# 27.net
KiCad netlist of a schematic drawn in Altium Designer
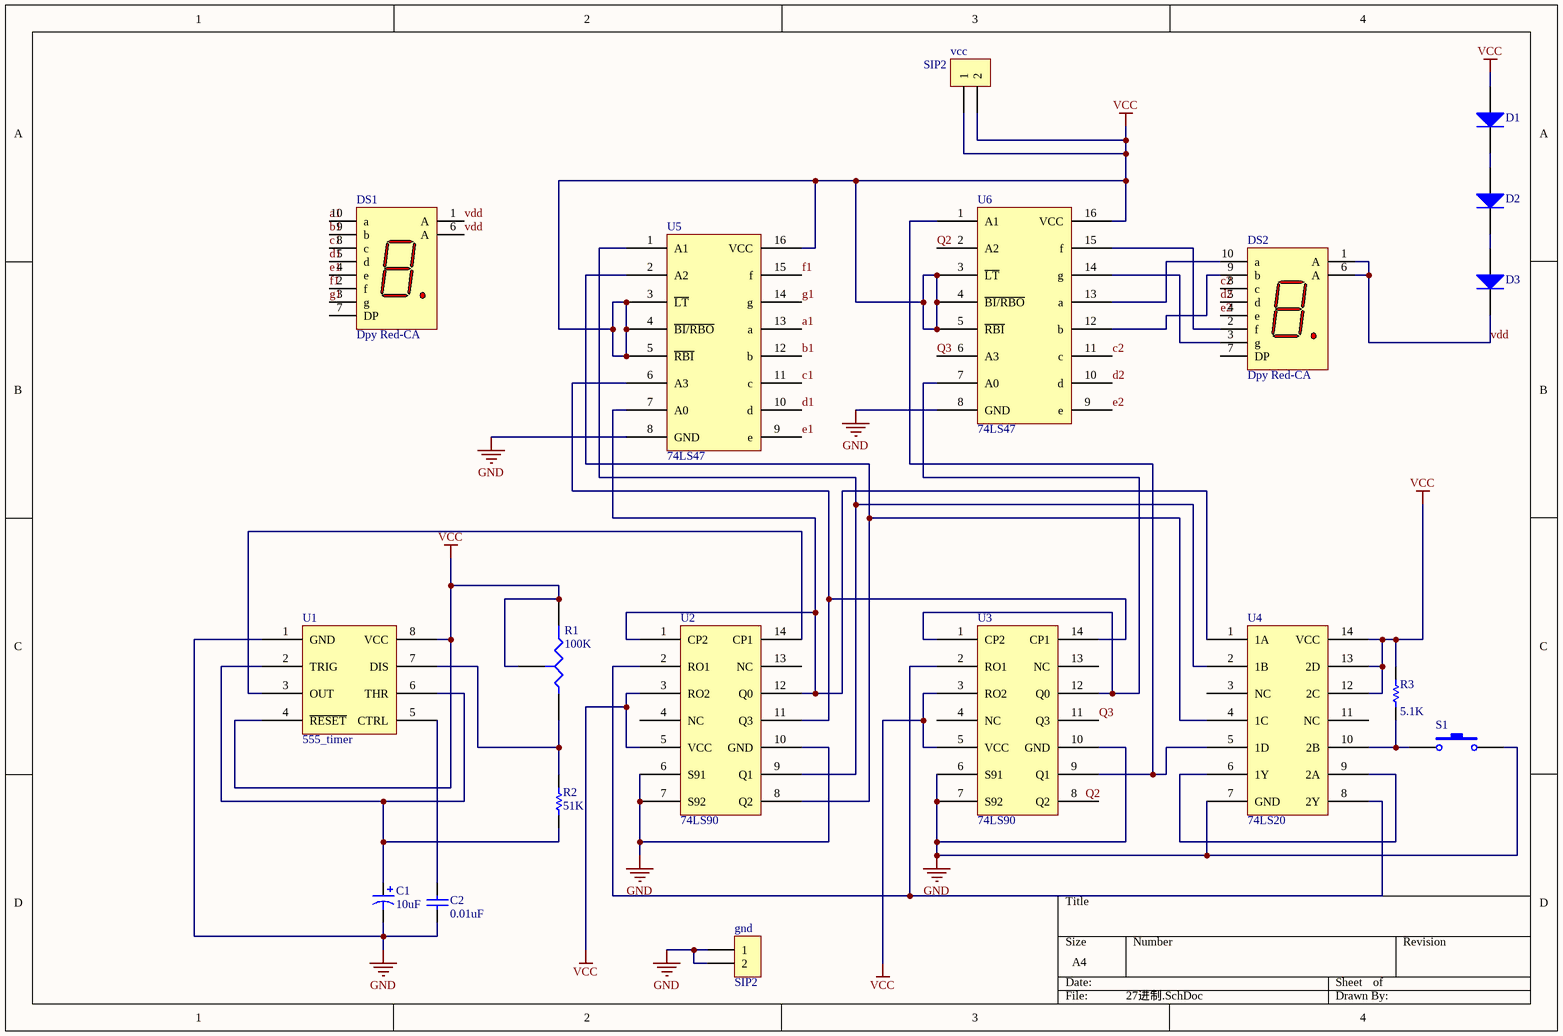
[diagram p0: 27进制.SchDoc]

(export (version "E")
  (design (tool "Eeschema 10.0.6"))
  (components
    (comp (ref "C1")
      (value "10uF")
      (footprint "RB7.6-15")
      (description "Polarized Capacitor (Radial)")
      (fields (field (name "Comment") "Cap Pol1") (field (name "PUBLISHER") "Altium Limited"))
      (libsource (lib "Miscellaneous Devices") (part "Cap Pol1"))
    )
    (comp (ref "C2")
      (value "0.01uF")
      (footprint "RAD-0.3")
      (description "Capacitor")
      (fields (field (name "Comment") "Cap") (field (name "PUBLISHER") "Altium Limited"))
      (libsource (lib "Miscellaneous Devices") (part "Cap"))
    )
    (comp (ref "D1")
      (value "Diode 1N914")
      (footprint "DO-35")
      (description "High Conductance Fast Diode")
      (fields (field (name "PUBLISHER") "Altium Limited"))
      (libsource (lib "Miscellaneous Devices") (part "Diode 1N914"))
    )
    (comp (ref "D2")
      (value "Diode 1N914")
      (footprint "DO-35")
      (description "High Conductance Fast Diode")
      (fields (field (name "PUBLISHER") "Altium Limited"))
      (libsource (lib "Miscellaneous Devices") (part "Diode 1N914"))
    )
    (comp (ref "D3")
      (value "Diode 1N914")
      (footprint "DO-35")
      (description "High Conductance Fast Diode")
      (fields (field (name "PUBLISHER") "Altium Limited"))
      (libsource (lib "Miscellaneous Devices") (part "Diode 1N914"))
    )
    (comp (ref "DS1")
      (value "Dpy Red-CA")
      (footprint "A")
      (description "7.62 mm Black Surface HER 7-Segment Display: CA, RH DP")
      (fields (field (name "PUBLISHER") "Altium Limited"))
      (libsource (lib "Miscellaneous Devices") (part "Dpy Red-CA"))
    )
    (comp (ref "DS2")
      (value "Dpy Red-CA")
      (footprint "A")
      (description "7.62 mm Black Surface HER 7-Segment Display: CA, RH DP")
      (fields (field (name "PUBLISHER") "Altium Limited"))
      (libsource (lib "Miscellaneous Devices") (part "Dpy Red-CA"))
    )
    (comp (ref "gnd")
      (value "SIP2")
      (footprint "HDR1X2")
      (description "jointbar")
      (libsource (lib "") (part "SIP2_1"))
    )
    (comp (ref "R1")
      (value "100K")
      (footprint "TO-39")
      (description "Tapped Resistor")
      (fields (field (name "Comment") "Res Tap") (field (name "PUBLISHER") "Altium Limited"))
      (libsource (lib "Miscellaneous Devices") (part "Res Tap"))
    )
    (comp (ref "R2")
      (value "51K")
      (footprint "AXIAL-0.3")
      (description "Resistor")
      (fields (field (name "Comment") "Res1") (field (name "PUBLISHER") "Altium Limited"))
      (libsource (lib "Miscellaneous Devices") (part "Res1"))
    )
    (comp (ref "R3")
      (value "5.1K")
      (footprint "AXIAL-0.3")
      (description "Resistor")
      (fields (field (name "Comment") "Res1") (field (name "PUBLISHER") "Altium Limited"))
      (libsource (lib "Miscellaneous Devices") (part "Res1"))
    )
    (comp (ref "S1")
      (value "SW-PB")
      (footprint "SPST-2")
      (description "Switch")
      (fields (field (name "PUBLISHER") "Altium Limited"))
      (libsource (lib "Miscellaneous Devices") (part "SW-PB"))
    )
    (comp (ref "U1") (value "555_timer") (footprint "DIP-8") (libsource (lib "数电") (part "555_timer")))
    (comp (ref "U2") (value "74LS90") (footprint "DIP-14") (libsource (lib "数电") (part "74LS90")))
    (comp (ref "U3") (value "74LS90") (footprint "DIP-14") (libsource (lib "数电") (part "74LS90")))
    (comp (ref "U4") (value "74LS20") (footprint "DIP-14") (libsource (lib "数电") (part "74LS20")))
    (comp (ref "U5") (value "74LS47") (footprint "DIP-16") (libsource (lib "数电") (part "74LS47")))
    (comp (ref "U6") (value "74LS47") (footprint "DIP-16") (libsource (lib "数电") (part "74LS47")))
    (comp (ref "vcc")
      (value "SIP2")
      (footprint "HDR1X2")
      (description "jointbar")
      (libsource (lib "温度") (part "SIP2"))
    )
  )
  (nets
    (net (code "1") (name "/Q2") (class "Default")
      (node (ref "U6") (pin "2") (pinfunction "A2_2") (pintype "passive"))
    )
    (net (code "2") (name "/Q3") (class "Default")
      (node (ref "U3") (pin "11") (pinfunction "Q3_11") (pintype "passive"))
      (node (ref "U6") (pin "6") (pinfunction "A3_6") (pintype "passive"))
    )
    (net (code "3") (name "/a1") (class "Default")
      (node (ref "DS1") (pin "10") (pinfunction "a_10") (pintype "passive"))
      (node (ref "U5") (pin "13") (pinfunction "a_13") (pintype "passive"))
    )
    (net (code "4") (name "/b1") (class "Default")
      (node (ref "DS1") (pin "9") (pinfunction "b_9") (pintype "passive"))
      (node (ref "U5") (pin "12") (pinfunction "b_12") (pintype "passive"))
    )
    (net (code "5") (name "/c1") (class "Default")
      (node (ref "DS1") (pin "8") (pinfunction "c_8") (pintype "passive"))
      (node (ref "U5") (pin "11") (pinfunction "c_11") (pintype "passive"))
    )
    (net (code "6") (name "/c2") (class "Default")
      (node (ref "DS2") (pin "8") (pinfunction "c_8") (pintype "passive"))
      (node (ref "U6") (pin "11") (pinfunction "c_11") (pintype "passive"))
    )
    (net (code "7") (name "/d1") (class "Default")
      (node (ref "DS1") (pin "5") (pinfunction "d_5") (pintype "passive"))
      (node (ref "U5") (pin "10") (pinfunction "d_10") (pintype "passive"))
    )
    (net (code "8") (name "/d2") (class "Default")
      (node (ref "DS2") (pin "5") (pinfunction "d_5") (pintype "passive"))
      (node (ref "U6") (pin "10") (pinfunction "d_10") (pintype "passive"))
    )
    (net (code "9") (name "/e1") (class "Default")
      (node (ref "DS1") (pin "4") (pinfunction "e_4") (pintype "passive"))
      (node (ref "U5") (pin "9") (pinfunction "e_9") (pintype "passive"))
    )
    (net (code "10") (name "/e2") (class "Default")
      (node (ref "DS2") (pin "4") (pinfunction "e_4") (pintype "passive"))
      (node (ref "U6") (pin "9") (pinfunction "e_9") (pintype "passive"))
    )
    (net (code "11") (name "/f1") (class "Default")
      (node (ref "DS1") (pin "2") (pinfunction "f_2") (pintype "passive"))
      (node (ref "U5") (pin "15") (pinfunction "f_15") (pintype "passive"))
    )
    (net (code "12") (name "/g1") (class "Default")
      (node (ref "DS1") (pin "3") (pinfunction "g_3") (pintype "passive"))
      (node (ref "U5") (pin "14") (pinfunction "g_14") (pintype "passive"))
    )
    (net (code "13") (name "/vdd") (class "Default")
      (node (ref "D3") (pin "2") (pinfunction "K_2") (pintype "passive"))
      (node (ref "DS1") (pin "1") (pinfunction "A_1") (pintype "passive"))
      (node (ref "DS1") (pin "6") (pinfunction "A_6") (pintype "passive"))
      (node (ref "DS2") (pin "1") (pinfunction "A_1") (pintype "passive"))
      (node (ref "DS2") (pin "6") (pinfunction "A_6") (pintype "passive"))
    )
    (net (code "14") (name "GND") (class "Default")
      (node (ref "C1") (pin "2") (pinfunction "2_2") (pintype "passive"))
      (node (ref "C2") (pin "1") (pinfunction "1_1") (pintype "passive"))
      (node (ref "S1") (pin "2") (pinfunction "2_2") (pintype "passive"))
      (node (ref "U1") (pin "1") (pinfunction "GND_1") (pintype "passive"))
      (node (ref "U2") (pin "10") (pinfunction "GND_10") (pintype "passive"))
      (node (ref "U2") (pin "6") (pinfunction "S91_6") (pintype "passive"))
      (node (ref "U2") (pin "7") (pinfunction "S92_7") (pintype "passive"))
      (node (ref "U3") (pin "10") (pinfunction "GND_10") (pintype "passive"))
      (node (ref "U3") (pin "6") (pinfunction "S91_6") (pintype "passive"))
      (node (ref "U3") (pin "7") (pinfunction "S92_7") (pintype "passive"))
      (node (ref "U4") (pin "7") (pinfunction "GND_7") (pintype "passive"))
      (node (ref "U5") (pin "8") (pinfunction "GND_8") (pintype "passive"))
      (node (ref "U6") (pin "8") (pinfunction "GND_8") (pintype "passive"))
      (node (ref "gnd") (pin "1") (pinfunction "1_1") (pintype "passive"))
      (node (ref "gnd") (pin "2") (pinfunction "2_2") (pintype "passive"))
    )
    (net (code "15") (name "Net-(D1-K)") (class "Default")
      (node (ref "D1") (pin "2") (pinfunction "K_2") (pintype "passive"))
      (node (ref "D2") (pin "1") (pinfunction "A_1") (pintype "passive"))
    )
    (net (code "16") (name "Net-(D2-K)") (class "Default")
      (node (ref "D2") (pin "2") (pinfunction "K_2") (pintype "passive"))
      (node (ref "D3") (pin "1") (pinfunction "A_1") (pintype "passive"))
    )
    (net (code "17") (name "Net-(DS2-a)") (class "Default")
      (node (ref "DS2") (pin "10") (pinfunction "a_10") (pintype "passive"))
      (node (ref "U6") (pin "13") (pinfunction "a_13") (pintype "passive"))
    )
    (net (code "18") (name "Net-(DS2-b)") (class "Default")
      (node (ref "DS2") (pin "9") (pinfunction "b_9") (pintype "passive"))
      (node (ref "U6") (pin "12") (pinfunction "b_12") (pintype "passive"))
    )
    (net (code "19") (name "Net-(DS2-f)") (class "Default")
      (node (ref "DS2") (pin "2") (pinfunction "f_2") (pintype "passive"))
      (node (ref "U6") (pin "15") (pinfunction "f_15") (pintype "passive"))
    )
    (net (code "20") (name "Net-(DS2-g)") (class "Default")
      (node (ref "DS2") (pin "3") (pinfunction "g_3") (pintype "passive"))
      (node (ref "U6") (pin "14") (pinfunction "g_14") (pintype "passive"))
    )
    (net (code "21") (name "Net-(R1-A)") (class "Default")
      (node (ref "R1") (pin "1") (pinfunction "A_1") (pintype "passive"))
      (node (ref "R2") (pin "2") (pinfunction "2_2") (pintype "passive"))
      (node (ref "U1") (pin "7") (pinfunction "DIS_7") (pintype "passive"))
    )
    (net (code "22") (name "Net-(U1-CTRL)") (class "Default")
      (node (ref "C2") (pin "2") (pinfunction "2_2") (pintype "passive"))
      (node (ref "U1") (pin "5") (pinfunction "CTRL_5") (pintype "passive"))
    )
    (net (code "23") (name "Net-(U1-OUT)") (class "Default")
      (node (ref "U1") (pin "3") (pinfunction "OUT_3") (pintype "passive"))
      (node (ref "U2") (pin "14") (pinfunction "CP1_14") (pintype "passive"))
    )
    (net (code "24") (name "Net-(U1-THR)") (class "Default")
      (node (ref "C1") (pin "1") (pinfunction "1_1") (pintype "passive"))
      (node (ref "R2") (pin "1") (pinfunction "1_1") (pintype "passive"))
      (node (ref "U1") (pin "2") (pinfunction "TRIG_2") (pintype "passive"))
      (node (ref "U1") (pin "6") (pinfunction "THR_6") (pintype "passive"))
    )
    (net (code "25") (name "Net-(U2-CP2)") (class "Default")
      (node (ref "U2") (pin "1") (pinfunction "CP2_1") (pintype "passive"))
      (node (ref "U2") (pin "12") (pinfunction "Q0_12") (pintype "passive"))
      (node (ref "U4") (pin "1") (pinfunction "1A_1") (pintype "passive"))
      (node (ref "U5") (pin "7") (pinfunction "A0_7") (pintype "passive"))
    )
    (net (code "26") (name "Net-(U2-Q1)") (class "Default")
      (node (ref "U2") (pin "9") (pinfunction "Q1_9") (pintype "passive"))
      (node (ref "U4") (pin "2") (pinfunction "1B_2") (pintype "passive"))
      (node (ref "U5") (pin "1") (pinfunction "A1_1") (pintype "passive"))
    )
    (net (code "27") (name "Net-(U2-Q2)") (class "Default")
      (node (ref "U2") (pin "8") (pinfunction "Q2_8") (pintype "passive"))
      (node (ref "U4") (pin "4") (pinfunction "1C_4") (pintype "passive"))
      (node (ref "U5") (pin "2") (pinfunction "A2_2") (pintype "passive"))
    )
    (net (code "28") (name "Net-(U2-Q3)") (class "Default")
      (node (ref "U2") (pin "11") (pinfunction "Q3_11") (pintype "passive"))
      (node (ref "U3") (pin "14") (pinfunction "CP1_14") (pintype "passive"))
      (node (ref "U5") (pin "6") (pinfunction "A3_6") (pintype "passive"))
    )
    (net (code "29") (name "Net-(U2-RO1)") (class "Default")
      (node (ref "U2") (pin "2") (pinfunction "RO1_2") (pintype "passive"))
      (node (ref "U3") (pin "2") (pinfunction "RO1_2") (pintype "passive"))
      (node (ref "U4") (pin "8") (pinfunction "2Y_8") (pintype "passive"))
    )
    (net (code "30") (name "Net-(U3-CP2)") (class "Default")
      (node (ref "U3") (pin "1") (pinfunction "CP2_1") (pintype "passive"))
      (node (ref "U3") (pin "12") (pinfunction "Q0_12") (pintype "passive"))
      (node (ref "U6") (pin "7") (pinfunction "A0_7") (pintype "passive"))
    )
    (net (code "31") (name "Net-(U3-Q1)") (class "Default")
      (node (ref "U3") (pin "9") (pinfunction "Q1_9") (pintype "passive"))
      (node (ref "U4") (pin "5") (pinfunction "1D_5") (pintype "passive"))
      (node (ref "U6") (pin "1") (pinfunction "A1_1") (pintype "passive"))
    )
    (net (code "32") (name "Net-(U4-1Y)") (class "Default")
      (node (ref "U4") (pin "6") (pinfunction "1Y_6") (pintype "passive"))
      (node (ref "U4") (pin "9") (pinfunction "2A_9") (pintype "passive"))
    )
    (net (code "33") (name "Net-(U4-2B)") (class "Default")
      (node (ref "R3") (pin "1") (pinfunction "1_1") (pintype "passive"))
      (node (ref "S1") (pin "1") (pinfunction "1_1") (pintype "passive"))
      (node (ref "U4") (pin "10") (pinfunction "2B_10") (pintype "passive"))
    )
    (net (code "34") (name "VCC") (class "Default")
      (node (ref "D1") (pin "1") (pinfunction "A_1") (pintype "passive"))
      (node (ref "R1") (pin "2") (pinfunction "B_2") (pintype "passive"))
      (node (ref "R1") (pin "3") (pinfunction "TAP_3") (pintype "passive"))
      (node (ref "R3") (pin "2") (pinfunction "2_2") (pintype "passive"))
      (node (ref "U1") (pin "4") (pinfunction "~{RESET}_4") (pintype "passive"))
      (node (ref "U1") (pin "8") (pinfunction "VCC_8") (pintype "passive"))
      (node (ref "U2") (pin "3") (pinfunction "RO2_3") (pintype "passive"))
      (node (ref "U2") (pin "5") (pinfunction "VCC_5") (pintype "passive"))
      (node (ref "U3") (pin "3") (pinfunction "RO2_3") (pintype "passive"))
      (node (ref "U3") (pin "5") (pinfunction "VCC_5") (pintype "passive"))
      (node (ref "U4") (pin "12") (pinfunction "2C_12") (pintype "passive"))
      (node (ref "U4") (pin "13") (pinfunction "2D_13") (pintype "passive"))
      (node (ref "U4") (pin "14") (pinfunction "VCC_14") (pintype "passive"))
      (node (ref "U5") (pin "16") (pinfunction "VCC_16") (pintype "passive"))
      (node (ref "U5") (pin "3") (pinfunction "~{LT}_3") (pintype "passive"))
      (node (ref "U5") (pin "4") (pinfunction "~{BI/RBO}_4") (pintype "passive"))
      (node (ref "U5") (pin "5") (pinfunction "~{RBI}_5") (pintype "passive"))
      (node (ref "U6") (pin "16") (pinfunction "VCC_16") (pintype "passive"))
      (node (ref "U6") (pin "3") (pinfunction "~{LT}_3") (pintype "passive"))
      (node (ref "U6") (pin "4") (pinfunction "~{BI/RBO}_4") (pintype "passive"))
      (node (ref "U6") (pin "5") (pinfunction "~{RBI}_5") (pintype "passive"))
      (node (ref "vcc") (pin "1") (pinfunction "1_1") (pintype "passive"))
      (node (ref "vcc") (pin "2") (pinfunction "2_2") (pintype "passive"))
    )
    (net (code "35") (name "unconnected-(DS1-DP-Pad7)") (class "Default")
      (node (ref "DS1") (pin "7") (pinfunction "DP_7") (pintype "passive"))
    )
    (net (code "36") (name "unconnected-(DS2-DP-Pad7)") (class "Default")
      (node (ref "DS2") (pin "7") (pinfunction "DP_7") (pintype "passive"))
    )
    (net (code "37") (name "unconnected-(U2-NC-Pad4)") (class "Default")
      (node (ref "U2") (pin "4") (pinfunction "NC_4") (pintype "passive"))
    )
    (net (code "38") (name "unconnected-(U2-NC-Pad13)") (class "Default")
      (node (ref "U2") (pin "13") (pinfunction "NC_13") (pintype "passive"))
    )
    (net (code "39") (name "unconnected-(U3-NC-Pad4)") (class "Default")
      (node (ref "U3") (pin "4") (pinfunction "NC_4") (pintype "passive"))
    )
    (net (code "40") (name "unconnected-(U3-NC-Pad13)") (class "Default")
      (node (ref "U3") (pin "13") (pinfunction "NC_13") (pintype "passive"))
    )
    (net (code "41") (name "unconnected-(U3-Q2-Pad8)") (class "Default")
      (node (ref "U3") (pin "8") (pinfunction "Q2_8") (pintype "passive"))
    )
    (net (code "42") (name "unconnected-(U4-NC-Pad3)") (class "Default")
      (node (ref "U4") (pin "3") (pinfunction "NC_3") (pintype "passive"))
    )
    (net (code "43") (name "unconnected-(U4-NC-Pad11)") (class "Default")
      (node (ref "U4") (pin "11") (pinfunction "NC_11") (pintype "passive"))
    )
  )
)
